# decoder.net
KiCad netlist of a schematic drawn in EAGLE
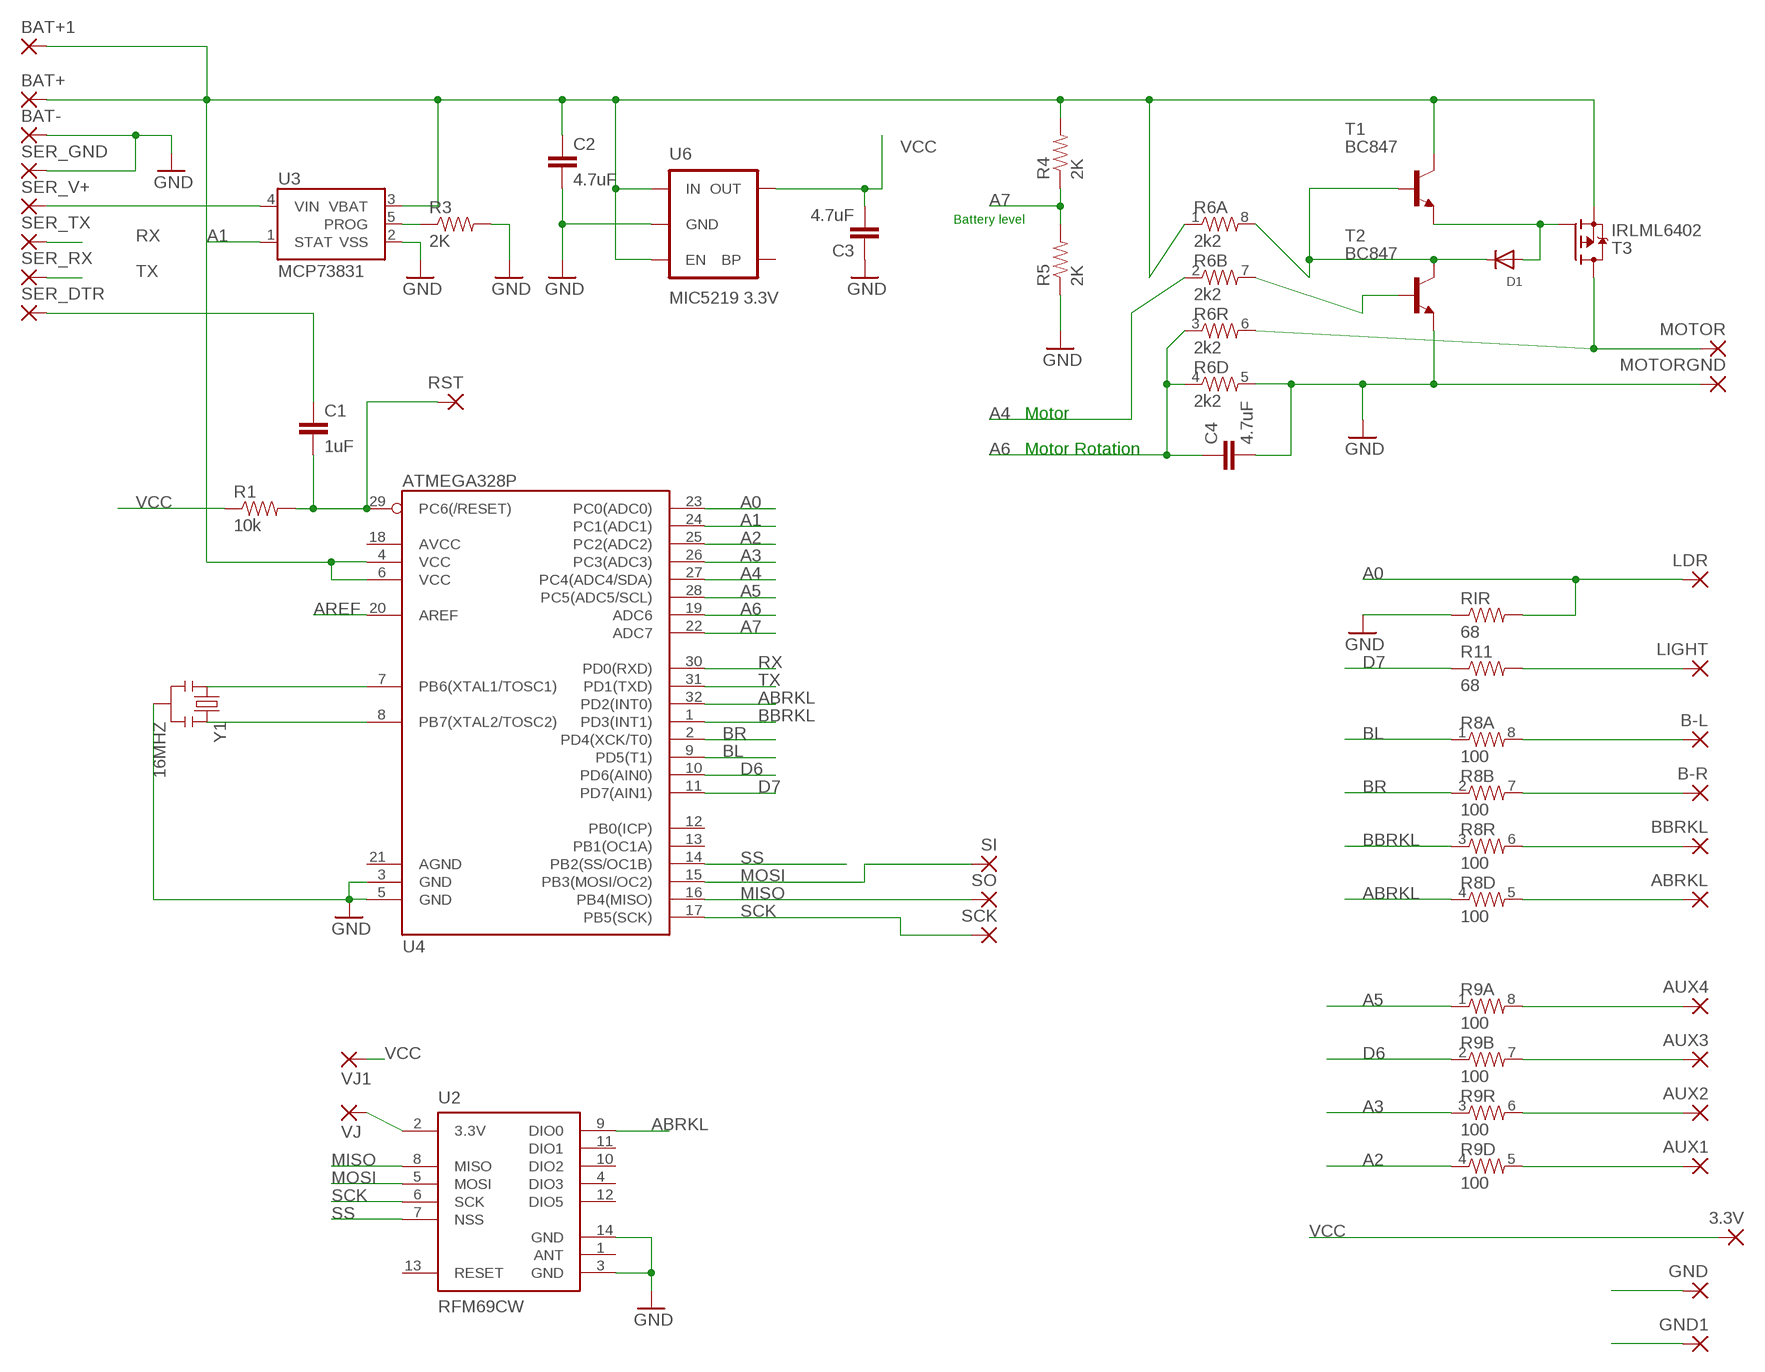
[diagram p0: schematic, sheet 1]

(export (version "E")
  (design (tool "Eeschema 10.0.6"))
  (components
    (comp (ref "3.3V")
      (value "SMD2")
      (footprint "eagle-import:SMD1,27-2,54")
      (libsource (lib "eagle-import") (part "SMD2"))
    )
    (comp (ref "ABRKL")
      (value "SMD2")
      (footprint "eagle-import:SMD1,27-2,54")
      (libsource (lib "eagle-import") (part "SMD2"))
    )
    (comp (ref "AUX1")
      (value "SMD2")
      (footprint "eagle-import:SMD1,27-2,54")
      (libsource (lib "eagle-import") (part "SMD2"))
    )
    (comp (ref "AUX2")
      (value "SMD2")
      (footprint "eagle-import:SMD1,27-2,54")
      (libsource (lib "eagle-import") (part "SMD2"))
    )
    (comp (ref "AUX3")
      (value "SMD2")
      (footprint "eagle-import:SMD1,27-2,54")
      (libsource (lib "eagle-import") (part "SMD2"))
    )
    (comp (ref "AUX4")
      (value "SMD2")
      (footprint "eagle-import:SMD1,27-2,54")
      (libsource (lib "eagle-import") (part "SMD2"))
    )
    (comp (ref "B-L")
      (value "SMD2")
      (footprint "eagle-import:SMD1,27-2,54")
      (libsource (lib "eagle-import") (part "SMD2"))
    )
    (comp (ref "B-R")
      (value "SMD2")
      (footprint "eagle-import:SMD1,27-2,54")
      (libsource (lib "eagle-import") (part "SMD2"))
    )
    (comp (ref "BAT+")
      (value "SMD2")
      (footprint "eagle-import:SMD1,27-2,54")
      (libsource (lib "eagle-import") (part "SMD2"))
    )
    (comp (ref "BAT+1")
      (value "SMD2")
      (footprint "eagle-import:SMD1,27-2,54")
      (libsource (lib "eagle-import") (part "SMD2"))
    )
    (comp (ref "BAT-")
      (value "SMD2")
      (footprint "eagle-import:SMD1,27-2,54")
      (libsource (lib "eagle-import") (part "SMD2"))
    )
    (comp (ref "BBRKL")
      (value "SMD2")
      (footprint "eagle-import:SMD1,27-2,54")
      (libsource (lib "eagle-import") (part "SMD2"))
    )
    (comp (ref "C1")
      (value "1uF")
      (footprint "eagle-import:0805")
      (libsource (lib "eagle-import") (part "CAP0805"))
    )
    (comp (ref "C2")
      (value "4.7uF")
      (footprint "eagle-import:0805")
      (libsource (lib "eagle-import") (part "CAP0805"))
    )
    (comp (ref "C3")
      (value "4.7uF")
      (footprint "eagle-import:0805")
      (libsource (lib "eagle-import") (part "CAP0805"))
    )
    (comp (ref "C4")
      (value "4.7uF")
      (footprint "eagle-import:0805")
      (libsource (lib "eagle-import") (part "CAP0805"))
    )
    (comp (ref "D1")
      (value "DIODESOD-523")
      (footprint "eagle-import:SOD-523")
      (libsource (lib "eagle-import") (part "DIODESOD-523"))
    )
    (comp (ref "GND")
      (value "SMD2")
      (footprint "eagle-import:SMD1,27-2,54")
      (libsource (lib "eagle-import") (part "SMD2"))
    )
    (comp (ref "GND1")
      (value "SMD2")
      (footprint "eagle-import:SMD1,27-2,54")
      (libsource (lib "eagle-import") (part "SMD2"))
    )
    (comp (ref "LDR")
      (value "SMD2")
      (footprint "eagle-import:SMD1,27-2,54")
      (libsource (lib "eagle-import") (part "SMD2"))
    )
    (comp (ref "LIGHT")
      (value "SMD2")
      (footprint "eagle-import:SMD1,27-2,54")
      (libsource (lib "eagle-import") (part "SMD2"))
    )
    (comp (ref "MOTOR")
      (value "SMD2")
      (footprint "eagle-import:SMD1,27-2,54")
      (libsource (lib "eagle-import") (part "SMD2"))
    )
    (comp (ref "MOTORGND")
      (value "SMD2")
      (footprint "eagle-import:SMD1,27-2,54")
      (libsource (lib "eagle-import") (part "SMD2"))
    )
    (comp (ref "R1")
      (value "10k")
      (footprint "eagle-import:0603-RES")
      (libsource (lib "eagle-import") (part "RESISTOR0603-RES"))
    )
    (comp (ref "R3")
      (value "2K")
      (footprint "eagle-import:0603-RES")
      (libsource (lib "eagle-import") (part "RESISTOR0603-RES"))
    )
    (comp (ref "R4")
      (value "2K")
      (footprint "eagle-import:0603-RES")
      (libsource (lib "eagle-import") (part "RESISTOR0603-RES"))
    )
    (comp (ref "R5")
      (value "2K")
      (footprint "eagle-import:0603-RES")
      (libsource (lib "eagle-import") (part "RESISTOR0603-RES"))
    )
    (comp (ref "R6")
      (value "2k2")
      (footprint "eagle-import:0603-ARV")
      (libsource (lib "eagle-import") (part "RESISTOR-ARRAY0603-ARV"))
    )
    (comp (ref "R8")
      (value "100")
      (footprint "eagle-import:0603-ARV")
      (libsource (lib "eagle-import") (part "RESISTOR-ARRAY0603-ARV"))
    )
    (comp (ref "R9")
      (value "100")
      (footprint "eagle-import:0603-ARV")
      (libsource (lib "eagle-import") (part "RESISTOR-ARRAY0603-ARV"))
    )
    (comp (ref "R11")
      (value "68")
      (footprint "eagle-import:0603-RES")
      (libsource (lib "eagle-import") (part "RESISTOR0603-RES"))
    )
    (comp (ref "RIR")
      (value "68")
      (footprint "eagle-import:0603-RES")
      (libsource (lib "eagle-import") (part "RESISTOR0603-RES"))
    )
    (comp (ref "RST")
      (value "SMD2")
      (footprint "eagle-import:SMD1,27-2,54")
      (libsource (lib "eagle-import") (part "SMD2"))
    )
    (comp (ref "SCK")
      (value "SMD2")
      (footprint "eagle-import:SMD1,27-2,54")
      (libsource (lib "eagle-import") (part "SMD2"))
    )
    (comp (ref "SER_DTR")
      (value "SMD2")
      (footprint "eagle-import:SMD1,27-2,54")
      (libsource (lib "eagle-import") (part "SMD2"))
    )
    (comp (ref "SER_GND")
      (value "SMD2")
      (footprint "eagle-import:SMD1,27-2,54")
      (libsource (lib "eagle-import") (part "SMD2"))
    )
    (comp (ref "SER_RX")
      (value "SMD2")
      (footprint "eagle-import:SMD1,27-2,54")
      (libsource (lib "eagle-import") (part "SMD2"))
    )
    (comp (ref "SER_TX")
      (value "SMD2")
      (footprint "eagle-import:SMD1,27-2,54")
      (libsource (lib "eagle-import") (part "SMD2"))
    )
    (comp (ref "SER_V+")
      (value "SMD2")
      (footprint "eagle-import:SMD1,27-2,54")
      (libsource (lib "eagle-import") (part "SMD2"))
    )
    (comp (ref "SI")
      (value "SMD2")
      (footprint "eagle-import:SMD1,27-2,54")
      (libsource (lib "eagle-import") (part "SMD2"))
    )
    (comp (ref "SO")
      (value "SMD2")
      (footprint "eagle-import:SMD1,27-2,54")
      (libsource (lib "eagle-import") (part "SMD2"))
    )
    (comp (ref "T1")
      (value "BC847")
      (footprint "eagle-import:SOT23")
      (libsource (lib "eagle-import") (part "BC847"))
    )
    (comp (ref "T2")
      (value "BC847")
      (footprint "eagle-import:SOT23")
      (libsource (lib "eagle-import") (part "BC847"))
    )
    (comp (ref "T3")
      (value "IRLML6402")
      (footprint "eagle-import:SOT23")
      (libsource (lib "eagle-import") (part "MOSFET-P-SOT23"))
    )
    (comp (ref "U2")
      (value "RFM69CW")
      (footprint "eagle-import:RFM69CW-XXXS2")
      (libsource (lib "eagle-import") (part "RFM69CW"))
    )
    (comp (ref "U3")
      (value "MCP73831")
      (footprint "eagle-import:SOT23-5")
      (libsource (lib "eagle-import") (part "MCP73831"))
    )
    (comp (ref "U4")
      (value "ATMEGA328P")
      (footprint "eagle-import:TQFP32-08")
      (libsource (lib "eagle-import") (part "ATMEGA328_SMT"))
    )
    (comp (ref "U6")
      (value "MIC5219 3.3V")
      (footprint "eagle-import:SOT23-5")
      (libsource (lib "eagle-import") (part "V_REG_MIC52193.3V"))
    )
    (comp (ref "VJ")
      (value "SMD2")
      (footprint "eagle-import:SMD1,27-2,54")
      (libsource (lib "eagle-import") (part "SMD2"))
    )
    (comp (ref "VJ1")
      (value "SMD2")
      (footprint "eagle-import:SMD1,27-2,54")
      (libsource (lib "eagle-import") (part "SMD2"))
    )
    (comp (ref "Y1")
      (value "16MHZ")
      (footprint "eagle-import:RESONATOR-SMD")
      (libsource (lib "eagle-import") (part "RESONATOR16MHZ"))
    )
  )
  (nets
    (net (code "1") (name "/A0") (class "Default")
      (node (ref "LDR") (pin "1") (pinfunction "P_1") (pintype "passive"))
      (node (ref "RIR") (pin "2") (pinfunction "2_2") (pintype "passive"))
      (node (ref "U4") (pin "23") (pinfunction "PC0(ADC0)_23") (pintype "bidirectional"))
    )
    (net (code "2") (name "/A1") (class "Default")
      (node (ref "U3") (pin "1") (pinfunction "STAT_1") (pintype "output"))
      (node (ref "U4") (pin "24") (pinfunction "PC1(ADC1)_24") (pintype "bidirectional"))
    )
    (net (code "3") (name "/A2") (class "Default")
      (node (ref "R9") (pin "4") (pinfunction "1_4") (pintype "passive"))
      (node (ref "U4") (pin "25") (pinfunction "PC2(ADC2)_25") (pintype "bidirectional"))
    )
    (net (code "4") (name "/A3") (class "Default")
      (node (ref "R9") (pin "3") (pinfunction "1_3") (pintype "passive"))
      (node (ref "U4") (pin "26") (pinfunction "PC3(ADC3)_26") (pintype "bidirectional"))
    )
    (net (code "5") (name "/A4") (class "Default")
      (node (ref "R6") (pin "2") (pinfunction "1_2") (pintype "passive"))
      (node (ref "U4") (pin "27") (pinfunction "PC4(ADC4/SDA)_27") (pintype "bidirectional"))
    )
    (net (code "6") (name "/A5") (class "Default")
      (node (ref "R9") (pin "1") (pinfunction "1_1") (pintype "passive"))
      (node (ref "U4") (pin "28") (pinfunction "PC5(ADC5/SCL)_28") (pintype "bidirectional"))
    )
    (net (code "7") (name "/A6") (class "Default")
      (node (ref "C4") (pin "1") (pinfunction "1_1") (pintype "passive"))
      (node (ref "R6") (pin "3") (pinfunction "1_3") (pintype "passive"))
      (node (ref "R6") (pin "4") (pinfunction "1_4") (pintype "passive"))
      (node (ref "U4") (pin "19") (pinfunction "ADC6_19") (pintype "bidirectional"))
    )
    (net (code "8") (name "/A7") (class "Default")
      (node (ref "R4") (pin "1") (pinfunction "1_1") (pintype "passive"))
      (node (ref "R5") (pin "2") (pinfunction "2_2") (pintype "passive"))
      (node (ref "U4") (pin "22") (pinfunction "ADC7_22") (pintype "bidirectional"))
    )
    (net (code "9") (name "/ABRKL") (class "Default")
      (node (ref "R8") (pin "4") (pinfunction "1_4") (pintype "passive"))
      (node (ref "U2") (pin "9") (pinfunction "DIO0_9") (pintype "bidirectional"))
      (node (ref "U4") (pin "32") (pinfunction "PD2(INT0)_32") (pintype "bidirectional"))
    )
    (net (code "10") (name "/AREF") (class "Default")
      (node (ref "U4") (pin "20") (pinfunction "AREF_20") (pintype "bidirectional"))
    )
    (net (code "11") (name "/BBRKL") (class "Default")
      (node (ref "R8") (pin "3") (pinfunction "1_3") (pintype "passive"))
      (node (ref "U4") (pin "1") (pinfunction "PD3(INT1)_1") (pintype "bidirectional"))
    )
    (net (code "12") (name "/BL") (class "Default")
      (node (ref "R8") (pin "1") (pinfunction "1_1") (pintype "passive"))
      (node (ref "U4") (pin "9") (pinfunction "PD5(T1)_9") (pintype "bidirectional"))
    )
    (net (code "13") (name "/BR") (class "Default")
      (node (ref "R8") (pin "2") (pinfunction "1_2") (pintype "passive"))
      (node (ref "U4") (pin "2") (pinfunction "PD4(XCK/T0)_2") (pintype "bidirectional"))
    )
    (net (code "14") (name "/D6") (class "Default")
      (node (ref "R9") (pin "2") (pinfunction "1_2") (pintype "passive"))
      (node (ref "U4") (pin "10") (pinfunction "PD6(AIN0)_10") (pintype "bidirectional"))
    )
    (net (code "15") (name "/D7") (class "Default")
      (node (ref "R11") (pin "1") (pinfunction "1_1") (pintype "passive"))
      (node (ref "U4") (pin "11") (pinfunction "PD7(AIN1)_11") (pintype "bidirectional"))
    )
    (net (code "16") (name "/MISO") (class "Default")
      (node (ref "SO") (pin "1") (pinfunction "P_1") (pintype "passive"))
      (node (ref "U2") (pin "8") (pinfunction "MISO_8") (pintype "bidirectional"))
      (node (ref "U4") (pin "16") (pinfunction "PB4(MISO)_16") (pintype "bidirectional"))
    )
    (net (code "17") (name "/MOSI") (class "Default")
      (node (ref "SI") (pin "1") (pinfunction "P_1") (pintype "passive"))
      (node (ref "U2") (pin "5") (pinfunction "MOSI_5") (pintype "input"))
      (node (ref "U4") (pin "15") (pinfunction "PB3(MOSI/OC2)_15") (pintype "bidirectional"))
    )
    (net (code "18") (name "/RX") (class "Default")
      (node (ref "SER_TX") (pin "1") (pinfunction "P_1") (pintype "passive"))
      (node (ref "U4") (pin "30") (pinfunction "PD0(RXD)_30") (pintype "bidirectional"))
    )
    (net (code "19") (name "/SCK") (class "Default")
      (node (ref "SCK") (pin "1") (pinfunction "P_1") (pintype "passive"))
      (node (ref "U2") (pin "6") (pinfunction "SCK_6") (pintype "input"))
      (node (ref "U4") (pin "17") (pinfunction "PB5(SCK)_17") (pintype "bidirectional"))
    )
    (net (code "20") (name "/SS") (class "Default")
      (node (ref "U2") (pin "7") (pinfunction "NSS_7") (pintype "input"))
      (node (ref "U4") (pin "14") (pinfunction "PB2(SS/OC1B)_14") (pintype "bidirectional"))
    )
    (net (code "21") (name "/TX") (class "Default")
      (node (ref "SER_RX") (pin "1") (pinfunction "P_1") (pintype "passive"))
      (node (ref "U4") (pin "31") (pinfunction "PD1(TXD)_31") (pintype "bidirectional"))
    )
    (net (code "22") (name "/VCC") (class "Default")
      (node (ref "3.3V") (pin "1") (pinfunction "P_1") (pintype "passive"))
      (node (ref "C3") (pin "2") (pinfunction "2_2") (pintype "passive"))
      (node (ref "R1") (pin "1") (pinfunction "1_1") (pintype "passive"))
      (node (ref "U6") (pin "5") (pinfunction "OUT_5") (pintype "passive"))
      (node (ref "VJ1") (pin "1") (pinfunction "P_1") (pintype "passive"))
    )
    (net (code "23") (name "GND") (class "Default")
      (node (ref "BAT-") (pin "1") (pinfunction "P_1") (pintype "passive"))
      (node (ref "C2") (pin "2") (pinfunction "2_2") (pintype "passive"))
      (node (ref "C3") (pin "1") (pinfunction "1_1") (pintype "passive"))
      (node (ref "C4") (pin "2") (pinfunction "2_2") (pintype "passive"))
      (node (ref "GND") (pin "1") (pinfunction "P_1") (pintype "passive"))
      (node (ref "GND1") (pin "1") (pinfunction "P_1") (pintype "passive"))
      (node (ref "MOTORGND") (pin "1") (pinfunction "P_1") (pintype "passive"))
      (node (ref "R3") (pin "2") (pinfunction "2_2") (pintype "passive"))
      (node (ref "R5") (pin "1") (pinfunction "1_1") (pintype "passive"))
      (node (ref "R6") (pin "5") (pinfunction "2_5") (pintype "passive"))
      (node (ref "RIR") (pin "1") (pinfunction "1_1") (pintype "passive"))
      (node (ref "SER_GND") (pin "1") (pinfunction "P_1") (pintype "passive"))
      (node (ref "T2") (pin "2") (pinfunction "E_2") (pintype "passive"))
      (node (ref "U2") (pin "14") (pinfunction "GND_14") (pintype "power_in"))
      (node (ref "U2") (pin "3") (pinfunction "GND_3") (pintype "power_in"))
      (node (ref "U3") (pin "2") (pinfunction "VSS_2") (pintype "power_in"))
      (node (ref "U4") (pin "3") (pinfunction "GND_3") (pintype "bidirectional"))
      (node (ref "U4") (pin "5") (pinfunction "GND_5") (pintype "bidirectional"))
      (node (ref "U6") (pin "2") (pinfunction "GND_2") (pintype "input"))
      (node (ref "Y1") (pin "2") (pinfunction "2_2") (pintype "passive"))
    )
    (net (code "24") (name "Net-(ABRKL-P)") (class "Default")
      (node (ref "ABRKL") (pin "1") (pinfunction "P_1") (pintype "passive"))
      (node (ref "R8") (pin "5") (pinfunction "2_5") (pintype "passive"))
    )
    (net (code "25") (name "Net-(AUX1-P)") (class "Default")
      (node (ref "AUX1") (pin "1") (pinfunction "P_1") (pintype "passive"))
      (node (ref "R9") (pin "5") (pinfunction "2_5") (pintype "passive"))
    )
    (net (code "26") (name "Net-(AUX2-P)") (class "Default")
      (node (ref "AUX2") (pin "1") (pinfunction "P_1") (pintype "passive"))
      (node (ref "R9") (pin "6") (pinfunction "2_6") (pintype "passive"))
    )
    (net (code "27") (name "Net-(AUX3-P)") (class "Default")
      (node (ref "AUX3") (pin "1") (pinfunction "P_1") (pintype "passive"))
      (node (ref "R9") (pin "7") (pinfunction "2_7") (pintype "passive"))
    )
    (net (code "28") (name "Net-(AUX4-P)") (class "Default")
      (node (ref "AUX4") (pin "1") (pinfunction "P_1") (pintype "passive"))
      (node (ref "R9") (pin "8") (pinfunction "2_8") (pintype "passive"))
    )
    (net (code "29") (name "Net-(B-L-P)") (class "Default")
      (node (ref "B-L") (pin "1") (pinfunction "P_1") (pintype "passive"))
      (node (ref "R8") (pin "8") (pinfunction "2_8") (pintype "passive"))
    )
    (net (code "30") (name "Net-(B-R-P)") (class "Default")
      (node (ref "B-R") (pin "1") (pinfunction "P_1") (pintype "passive"))
      (node (ref "R8") (pin "7") (pinfunction "2_7") (pintype "passive"))
    )
    (net (code "31") (name "Net-(BAT+-P)") (class "Default")
      (node (ref "BAT+") (pin "1") (pinfunction "P_1") (pintype "passive"))
      (node (ref "BAT+1") (pin "1") (pinfunction "P_1") (pintype "passive"))
      (node (ref "C2") (pin "1") (pinfunction "1_1") (pintype "passive"))
      (node (ref "R4") (pin "2") (pinfunction "2_2") (pintype "passive"))
      (node (ref "R6") (pin "1") (pinfunction "1_1") (pintype "passive"))
      (node (ref "T1") (pin "3") (pinfunction "C_3") (pintype "passive"))
      (node (ref "T3") (pin "2") (pinfunction "S_2") (pintype "passive"))
      (node (ref "U3") (pin "3") (pinfunction "VBAT_3") (pintype "power_in"))
      (node (ref "U4") (pin "4") (pinfunction "VCC_4") (pintype "bidirectional"))
      (node (ref "U4") (pin "6") (pinfunction "VCC_6") (pintype "bidirectional"))
      (node (ref "U6") (pin "1") (pinfunction "IN_1") (pintype "input"))
      (node (ref "U6") (pin "3") (pinfunction "EN_3") (pintype "input"))
    )
    (net (code "32") (name "Net-(BBRKL-P)") (class "Default")
      (node (ref "BBRKL") (pin "1") (pinfunction "P_1") (pintype "passive"))
      (node (ref "R8") (pin "6") (pinfunction "2_6") (pintype "passive"))
    )
    (net (code "33") (name "Net-(D1-C)") (class "Default")
      (node (ref "D1") (pin "K") (pinfunction "C_K") (pintype "passive"))
      (node (ref "R6") (pin "8") (pinfunction "2_8") (pintype "passive"))
      (node (ref "T1") (pin "1") (pinfunction "B_1") (pintype "passive"))
      (node (ref "T2") (pin "3") (pinfunction "C_3") (pintype "passive"))
    )
    (net (code "34") (name "Net-(LIGHT-P)") (class "Default")
      (node (ref "LIGHT") (pin "1") (pinfunction "P_1") (pintype "passive"))
      (node (ref "R11") (pin "2") (pinfunction "2_2") (pintype "passive"))
    )
    (net (code "35") (name "Net-(MOTOR-P)") (class "Default")
      (node (ref "MOTOR") (pin "1") (pinfunction "P_1") (pintype "passive"))
      (node (ref "R6") (pin "6") (pinfunction "2_6") (pintype "passive"))
      (node (ref "T3") (pin "3") (pinfunction "D_3") (pintype "passive"))
    )
    (net (code "36") (name "Net-(R6B-2)") (class "Default")
      (node (ref "R6") (pin "7") (pinfunction "2_7") (pintype "passive"))
      (node (ref "T2") (pin "1") (pinfunction "B_1") (pintype "passive"))
    )
    (net (code "37") (name "Net-(RST-P)") (class "Default")
      (node (ref "C1") (pin "2") (pinfunction "2_2") (pintype "passive"))
      (node (ref "R1") (pin "2") (pinfunction "2_2") (pintype "passive"))
      (node (ref "RST") (pin "1") (pinfunction "P_1") (pintype "passive"))
      (node (ref "U4") (pin "29") (pinfunction "PC6(/RESET)_29") (pintype "bidirectional"))
    )
    (net (code "38") (name "Net-(SER_DTR-P)") (class "Default")
      (node (ref "C1") (pin "1") (pinfunction "1_1") (pintype "passive"))
      (node (ref "SER_DTR") (pin "1") (pinfunction "P_1") (pintype "passive"))
    )
    (net (code "39") (name "Net-(SER_V+-P)") (class "Default")
      (node (ref "SER_V+") (pin "1") (pinfunction "P_1") (pintype "passive"))
      (node (ref "U3") (pin "4") (pinfunction "VIN_4") (pintype "power_in"))
    )
    (net (code "40") (name "Net-(T1-E)") (class "Default")
      (node (ref "D1") (pin "A") (pinfunction "A_A") (pintype "passive"))
      (node (ref "T1") (pin "2") (pinfunction "E_2") (pintype "passive"))
      (node (ref "T3") (pin "1") (pinfunction "G_1") (pintype "passive"))
    )
    (net (code "41") (name "Net-(U2-3.3V)") (class "Default")
      (node (ref "U2") (pin "2") (pinfunction "3.3V_2") (pintype "power_in"))
      (node (ref "VJ") (pin "1") (pinfunction "P_1") (pintype "passive"))
    )
    (net (code "42") (name "Net-(U3-PROG)") (class "Default")
      (node (ref "R3") (pin "1") (pinfunction "1_1") (pintype "passive"))
      (node (ref "U3") (pin "5") (pinfunction "PROG_5") (pintype "input"))
    )
    (net (code "43") (name "Net-(U4-PB6(XTAL1{slash}TOSC1))") (class "Default")
      (node (ref "U4") (pin "7") (pinfunction "PB6(XTAL1/TOSC1)_7") (pintype "bidirectional"))
      (node (ref "Y1") (pin "1") (pinfunction "1_1") (pintype "passive"))
    )
    (net (code "44") (name "Net-(U4-PB7(XTAL2{slash}TOSC2))") (class "Default")
      (node (ref "U4") (pin "8") (pinfunction "PB7(XTAL2/TOSC2)_8") (pintype "bidirectional"))
      (node (ref "Y1") (pin "3") (pinfunction "3_3") (pintype "passive"))
    )
    (net (code "45") (name "unconnected-(U2-ANT-Pad1)") (class "Default")
      (node (ref "U2") (pin "1") (pinfunction "ANT_1") (pintype "passive"))
    )
    (net (code "46") (name "unconnected-(U2-DIO1-Pad11)") (class "Default")
      (node (ref "U2") (pin "11") (pinfunction "DIO1_11") (pintype "bidirectional"))
    )
    (net (code "47") (name "unconnected-(U2-DIO2-Pad10)") (class "Default")
      (node (ref "U2") (pin "10") (pinfunction "DIO2_10") (pintype "bidirectional"))
    )
    (net (code "48") (name "unconnected-(U2-DIO3-Pad4)") (class "Default")
      (node (ref "U2") (pin "4") (pinfunction "DIO3_4") (pintype "bidirectional"))
    )
    (net (code "49") (name "unconnected-(U2-DIO5-Pad12)") (class "Default")
      (node (ref "U2") (pin "12") (pinfunction "DIO5_12") (pintype "bidirectional"))
    )
    (net (code "50") (name "unconnected-(U2-RESET-Pad13)") (class "Default")
      (node (ref "U2") (pin "13") (pinfunction "RESET_13") (pintype "input"))
    )
    (net (code "51") (name "unconnected-(U4-AGND-Pad21)") (class "Default")
      (node (ref "U4") (pin "21") (pinfunction "AGND_21") (pintype "bidirectional"))
    )
    (net (code "52") (name "unconnected-(U4-AVCC-Pad18)") (class "Default")
      (node (ref "U4") (pin "18") (pinfunction "AVCC_18") (pintype "bidirectional"))
    )
    (net (code "53") (name "unconnected-(U4-PB0(ICP)-Pad12)") (class "Default")
      (node (ref "U4") (pin "12") (pinfunction "PB0(ICP)_12") (pintype "bidirectional"))
    )
    (net (code "54") (name "unconnected-(U4-PB1(OC1A)-Pad13)") (class "Default")
      (node (ref "U4") (pin "13") (pinfunction "PB1(OC1A)_13") (pintype "bidirectional"))
    )
    (net (code "55") (name "unconnected-(U6-BP-Pad4)") (class "Default")
      (node (ref "U6") (pin "4") (pinfunction "BP_4") (pintype "input"))
    )
  )
)
